# WIFIModule_M_V1_0.net
KiCad netlist of a schematic drawn in Altium Designer
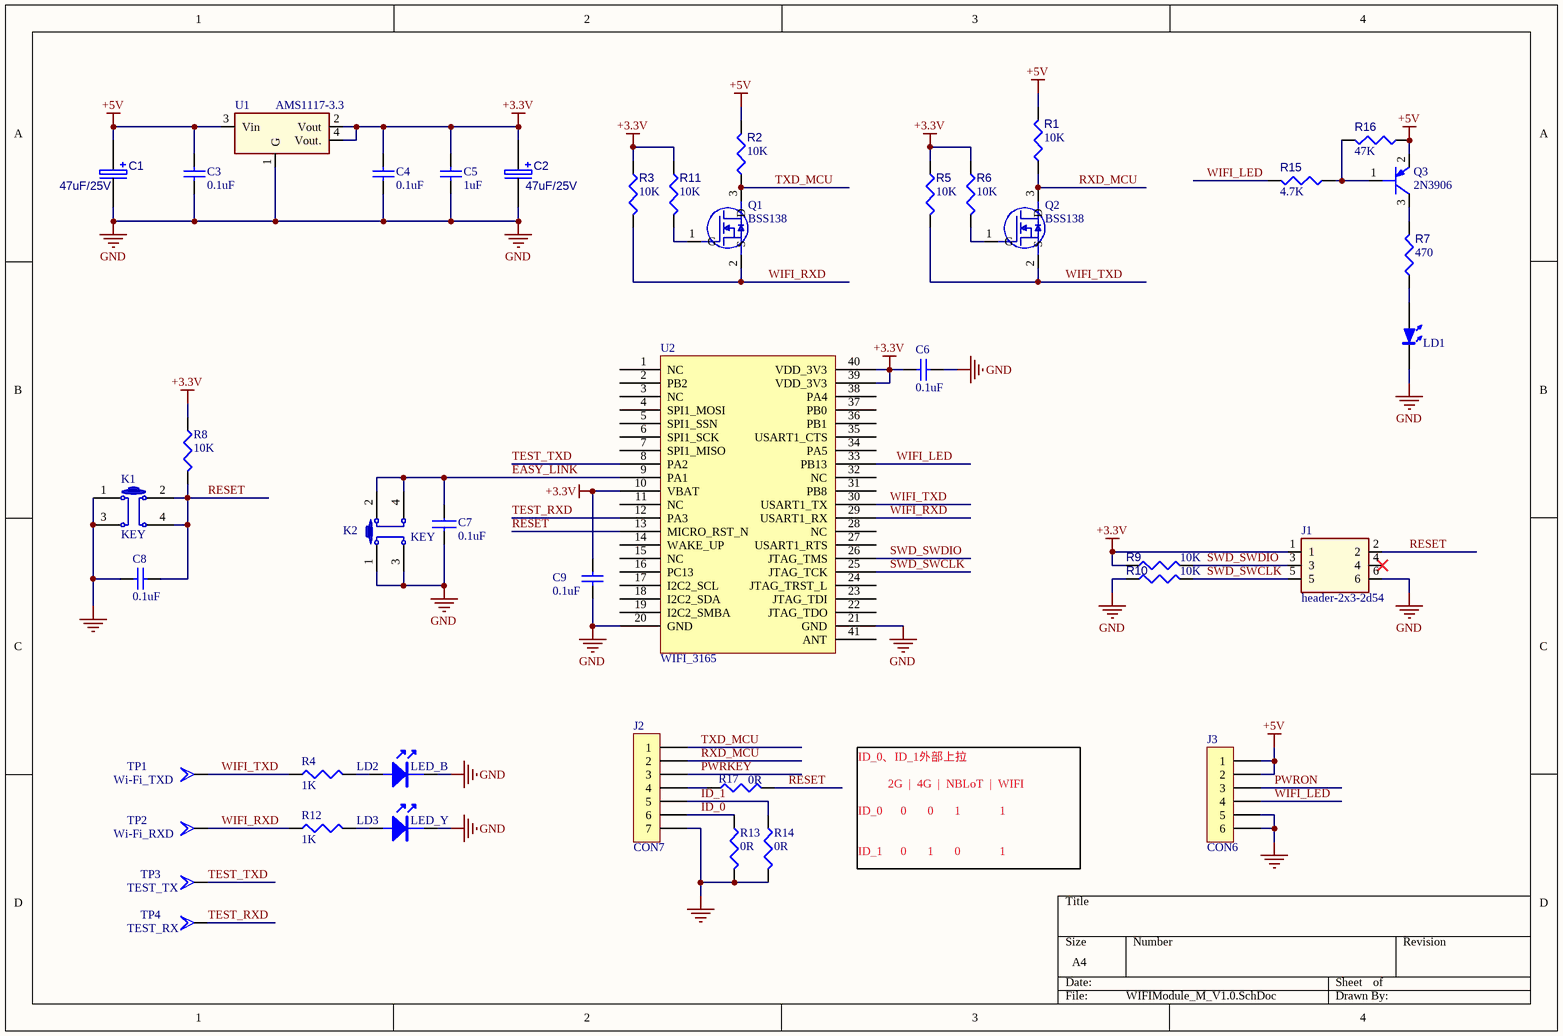
[diagram p0: WIFIModule_M_V1.0.SchDoc]

(export (version "E")
  (design (tool "Eeschema 10.0.6"))
  (components
    (comp (ref "C1")
      (value "47uF/25V")
      (footprint "C_TAN_B")
      (description "E-CAP")
      (libsource (lib "*") (part "ECAP"))
    )
    (comp (ref "C2")
      (value "47uF/25V")
      (footprint "C_TAN_B")
      (description "E-CAP")
      (libsource (lib "*") (part "ECAP"))
    )
    (comp (ref "C3")
      (value "0.1uF")
      (footprint "0603_C")
      (description "Capacitor")
      (fields (field (name "PUBLISHER") "Altium Limited"))
      (libsource (lib "EM_SENSOR_V3.01") (part "Cap Semi_1"))
    )
    (comp (ref "C4")
      (value "0.1uF")
      (footprint "0603_C")
      (description "Capacitor")
      (fields (field (name "PUBLISHER") "Altium Limited"))
      (libsource (lib "EM_SENSOR_V3.01") (part "Cap Semi_1"))
    )
    (comp (ref "C5")
      (value "1uF")
      (footprint "0603_C")
      (description "Capacitor")
      (fields (field (name "PUBLISHER") "Altium Limited"))
      (libsource (lib "EM_SENSOR_V3.01") (part "Cap Semi_1"))
    )
    (comp (ref "C6")
      (value "0.1uF")
      (footprint "0603_C")
      (description "Capacitor")
      (fields (field (name "PUBLISHER") "Altium Limited"))
      (libsource (lib "EM_SENSOR_V3.01") (part "Cap Semi_1"))
    )
    (comp (ref "C7") (value "0.1uF") (footprint "0603_C") (libsource (lib "EM_SENSOR_V4.1") (part "CAP NP")))
    (comp (ref "C8")
      (value "0.1uF")
      (footprint "0603_C")
      (description "Capacitor")
      (fields (field (name "PUBLISHER") "Altium Limited"))
      (libsource (lib "Miscellaneous Devices") (part "Cap"))
    )
    (comp (ref "C9")
      (value "0.1uF")
      (footprint "0603_C")
      (description "Capacitor")
      (fields (field (name "PUBLISHER") "Altium Limited"))
      (libsource (lib "EM_SENSOR_V2.03") (part "Cap Semi_1"))
    )
    (comp (ref "J1")
      (value "header-2x3-2d54")
      (footprint "HT8550_FLASH_LOADER")
      (libsource (lib "EM_SENSOR_V3.01") (part "header-2x3-2d54"))
    )
    (comp (ref "J2") (value "CON7") (footprint "SIP7") (libsource (lib "MySchlib") (part "CON7")))
    (comp (ref "J3") (value "CON6") (footprint "SIP6") (libsource (lib "MySchlib") (part "CON6")))
    (comp (ref "K1") (value "KEY") (footprint "KEY_SMD5465") (libsource (lib "") (part "KEY_1")))
    (comp (ref "K2") (value "KEY") (footprint "KEY_SMD5465") (libsource (lib "Schlib1") (part "KEY")))
    (comp (ref "LD1")
      (value "WHITE")
      (footprint "LED_0603")
      (description "LED")
      (libsource (lib "*") (part "LED"))
    )
    (comp (ref "LD2") (value "LED_B") (footprint "LED_0603") (libsource (lib "EM_SENSOR_V2.03") (part "LED")))
    (comp (ref "LD3") (value "LED_Y") (footprint "LED_0603") (libsource (lib "EM_SENSOR_V2.03") (part "LED")))
    (comp (ref "Q1")
      (value "BSS138")
      (footprint "SOT23")
      (description "N-Channel Enhancement MOSFET")
      (libsource (lib "EP_MCB_V6.0") (part "N-Channel Enhancement MOSFET"))
    )
    (comp (ref "Q2")
      (value "BSS138")
      (footprint "SOT23")
      (description "N-Channel Enhancement MOSFET")
      (libsource (lib "EP_MCB_V6.0") (part "N-Channel Enhancement MOSFET"))
    )
    (comp (ref "Q3") (value "2N3906") (footprint "SOT23") (libsource (lib "MySchlib") (part "PNP")))
    (comp (ref "R1")
      (value "10K")
      (footprint "0603_R")
      (description "Resistor")
      (fields (field (name "PUBLISHER") "Altium Limited"))
      (libsource (lib "EP_MCB_V6.0") (part "Res3_3"))
    )
    (comp (ref "R2")
      (value "10K")
      (footprint "0603_R")
      (description "Resistor")
      (fields (field (name "PUBLISHER") "Altium Limited"))
      (libsource (lib "EP_MCB_V6.0") (part "Res3_3"))
    )
    (comp (ref "R3")
      (value "10K")
      (footprint "0603_R")
      (description "Resistor")
      (fields (field (name "PUBLISHER") "Altium Limited"))
      (libsource (lib "EP_MCB_V6.0") (part "Res3_3"))
    )
    (comp (ref "R4") (value "1K") (footprint "0603_R") (libsource (lib "EM_SENSOR_V2.01") (part "R")))
    (comp (ref "R5")
      (value "10K")
      (footprint "0603_R")
      (description "Resistor")
      (fields (field (name "PUBLISHER") "Altium Limited"))
      (libsource (lib "EP_MCB_V6.0") (part "Res3_3"))
    )
    (comp (ref "R6")
      (value "10K")
      (footprint "0603_R")
      (description "Resistor")
      (fields (field (name "PUBLISHER") "Altium Limited"))
      (libsource (lib "EP_MCB_V6.0") (part "Res3_3"))
    )
    (comp (ref "R7")
      (value "470")
      (footprint "0603_R")
      (description "Resistor")
      (fields (field (name "PUBLISHER") "Altium Limited"))
      (libsource (lib "EM_SENSOR_V3.01") (part "Res3"))
    )
    (comp (ref "R8")
      (value "10K")
      (footprint "0603_R")
      (description "Resistor")
      (fields (field (name "PUBLISHER") "Altium Limited"))
      (libsource (lib "Miscellaneous Devices") (part "Res3"))
    )
    (comp (ref "R9")
      (value "10K")
      (footprint "0603_R")
      (description "Resistor")
      (fields (field (name "PUBLISHER") "Altium Limited"))
      (libsource (lib "EM_SENSOR_V3.01") (part "Res3"))
    )
    (comp (ref "R10")
      (value "10K")
      (footprint "0603_R")
      (description "Resistor")
      (fields (field (name "PUBLISHER") "Altium Limited"))
      (libsource (lib "EM_SENSOR_V3.01") (part "Res3"))
    )
    (comp (ref "R11")
      (value "10K")
      (footprint "0603_R")
      (description "Resistor")
      (fields (field (name "PUBLISHER") "Altium Limited"))
      (libsource (lib "EP_MCB_V6.0") (part "Res3_3"))
    )
    (comp (ref "R12") (value "1K") (footprint "0603_R") (libsource (lib "EM_SENSOR_V2.01") (part "R")))
    (comp (ref "R13") (value "0R") (footprint "0603_R") (libsource (lib "MySchlib") (part "RES1")))
    (comp (ref "R14") (value "0R") (footprint "0603_R") (libsource (lib "MySchlib") (part "RES1")))
    (comp (ref "R15")
      (value "4.7K")
      (footprint "0603_R")
      (description "Resistor")
      (fields (field (name "PUBLISHER") "Altium Limited"))
      (libsource (lib "EM_SENSOR_V3.01") (part "Res3"))
    )
    (comp (ref "R16")
      (value "47K")
      (footprint "0603_R")
      (description "Resistor")
      (fields (field (name "PUBLISHER") "Altium Limited"))
      (libsource (lib "EM_SENSOR_V3.01") (part "Res3"))
    )
    (comp (ref "R17") (value "0R") (footprint "0603_R") (libsource (lib "MySchlib") (part "RES1")))
    (comp (ref "TP1")
      (value "Wi-Fi_TXD")
      (footprint "TP_60_30")
      (libsource (lib "EM_SENSOR_V2.01") (part "T POINT A"))
    )
    (comp (ref "TP2")
      (value "Wi-Fi_RXD")
      (footprint "TP_60_30")
      (libsource (lib "EM_SENSOR_V2.01") (part "T POINT A"))
    )
    (comp (ref "TP3")
      (value "TEST_TX")
      (footprint "TP_60_30")
      (libsource (lib "EM_SENSOR_V2.03") (part "T POINT A"))
    )
    (comp (ref "TP4")
      (value "TEST_RX")
      (footprint "TP_60_30")
      (libsource (lib "EM_SENSOR_V2.03") (part "T POINT A"))
    )
    (comp (ref "U1")
      (value "AMS1117-3.3")
      (footprint "SOT223")
      (libsource (lib "EM_SENSOR_V2.01") (part "AMS1117-3.3"))
    )
    (comp (ref "U2") (value "WIFI_3165") (footprint "EMW3165-P") (libsource (lib "*") (part "WIFI_3165")))
  )
  (nets
    (net (code "1") (name "+3.3V") (class "Default")
      (node (ref "C2") (pin "1") (pinfunction "+_1") (pintype "passive"))
      (node (ref "C4") (pin "1") (pinfunction "1_1") (pintype "passive"))
      (node (ref "C5") (pin "1") (pinfunction "1_1") (pintype "passive"))
      (node (ref "C6") (pin "2") (pinfunction "2_2") (pintype "passive"))
      (node (ref "C9") (pin "2") (pinfunction "2_2") (pintype "passive"))
      (node (ref "J1") (pin "1") (pinfunction "1_1") (pintype "passive"))
      (node (ref "R11") (pin "1") (pinfunction "1_1") (pintype "passive"))
      (node (ref "R3") (pin "1") (pinfunction "1_1") (pintype "passive"))
      (node (ref "R5") (pin "1") (pinfunction "1_1") (pintype "passive"))
      (node (ref "R6") (pin "1") (pinfunction "1_1") (pintype "passive"))
      (node (ref "R8") (pin "2") (pinfunction "2_2") (pintype "passive"))
      (node (ref "R9") (pin "1") (pinfunction "1_1") (pintype "passive"))
      (node (ref "U1") (pin "2") (pinfunction "Vout_2") (pintype "passive"))
      (node (ref "U1") (pin "4") (pinfunction "Vout._4") (pintype "passive"))
      (node (ref "U2") (pin "10") (pinfunction "VBAT_10") (pintype "passive"))
      (node (ref "U2") (pin "39") (pinfunction "VDD_3V3_39") (pintype "passive"))
      (node (ref "U2") (pin "40") (pinfunction "VDD_3V3_40") (pintype "passive"))
    )
    (net (code "2") (name "+5V") (class "Default")
      (node (ref "C1") (pin "1") (pinfunction "+_1") (pintype "passive"))
      (node (ref "C3") (pin "1") (pinfunction "1_1") (pintype "passive"))
      (node (ref "J3") (pin "1") (pinfunction "1_1") (pintype "passive"))
      (node (ref "J3") (pin "2") (pinfunction "2_2") (pintype "passive"))
      (node (ref "Q3") (pin "2") (pinfunction "EMITTER_2") (pintype "passive"))
      (node (ref "R1") (pin "2") (pinfunction "2_2") (pintype "passive"))
      (node (ref "R16") (pin "1") (pinfunction "1_1") (pintype "passive"))
      (node (ref "R2") (pin "2") (pinfunction "2_2") (pintype "passive"))
      (node (ref "U1") (pin "3") (pinfunction "Vin_3") (pintype "passive"))
    )
    (net (code "3") (name "/EASY_LINK") (class "Default")
      (node (ref "C7") (pin "1") (pinfunction "1_1") (pintype "passive"))
      (node (ref "K2") (pin "2") (pinfunction "2_2") (pintype "passive"))
      (node (ref "K2") (pin "4") (pinfunction "4_4") (pintype "passive"))
      (node (ref "U2") (pin "9") (pinfunction "PA1_9") (pintype "passive"))
    )
    (net (code "4") (name "/ID_0") (class "Default")
      (node (ref "J2") (pin "6") (pinfunction "6_6") (pintype "passive"))
      (node (ref "R13") (pin "1") (pinfunction "1_1") (pintype "passive"))
    )
    (net (code "5") (name "/ID_1") (class "Default")
      (node (ref "J2") (pin "5") (pinfunction "5_5") (pintype "passive"))
      (node (ref "R14") (pin "1") (pinfunction "1_1") (pintype "passive"))
    )
    (net (code "6") (name "/PWRKEY") (class "Default")
      (node (ref "J2") (pin "3") (pinfunction "3_3") (pintype "passive"))
    )
    (net (code "7") (name "/PWRON") (class "Default")
      (node (ref "J3") (pin "3") (pinfunction "3_3") (pintype "passive"))
    )
    (net (code "8") (name "/RESET") (class "Default")
      (node (ref "C8") (pin "2") (pinfunction "2_2") (pintype "passive"))
      (node (ref "J1") (pin "2") (pinfunction "2_2") (pintype "passive"))
      (node (ref "K1") (pin "2") (pinfunction "2_2") (pintype "passive"))
      (node (ref "K1") (pin "4") (pinfunction "4_4") (pintype "passive"))
      (node (ref "R17") (pin "2") (pinfunction "2_2") (pintype "passive"))
      (node (ref "R8") (pin "1") (pinfunction "1_1") (pintype "passive"))
      (node (ref "U2") (pin "13") (pinfunction "MICRO_RST_N_13") (pintype "passive"))
    )
    (net (code "9") (name "/RXD_MCU") (class "Default")
      (node (ref "J2") (pin "2") (pinfunction "2_2") (pintype "passive"))
      (node (ref "Q2") (pin "3") (pinfunction "D_3") (pintype "passive"))
      (node (ref "R1") (pin "1") (pinfunction "1_1") (pintype "passive"))
    )
    (net (code "10") (name "/SWD_SWCLK") (class "Default")
      (node (ref "J1") (pin "5") (pinfunction "5_5") (pintype "passive"))
      (node (ref "R10") (pin "2") (pinfunction "2_2") (pintype "passive"))
      (node (ref "U2") (pin "25") (pinfunction "JTAG_TCK_25") (pintype "passive"))
    )
    (net (code "11") (name "/SWD_SWDIO") (class "Default")
      (node (ref "J1") (pin "3") (pinfunction "3_3") (pintype "passive"))
      (node (ref "R9") (pin "2") (pinfunction "2_2") (pintype "passive"))
      (node (ref "U2") (pin "26") (pinfunction "JTAG_TMS_26") (pintype "passive"))
    )
    (net (code "12") (name "/TEST_RXD") (class "Default")
      (node (ref "TP4") (pin "1") (pinfunction "TP_1") (pintype "passive"))
      (node (ref "U2") (pin "12") (pinfunction "PA3_12") (pintype "passive"))
    )
    (net (code "13") (name "/TEST_TXD") (class "Default")
      (node (ref "TP3") (pin "1") (pinfunction "TP_1") (pintype "passive"))
      (node (ref "U2") (pin "8") (pinfunction "PA2_8") (pintype "passive"))
    )
    (net (code "14") (name "/TXD_MCU") (class "Default")
      (node (ref "J2") (pin "1") (pinfunction "1_1") (pintype "passive"))
      (node (ref "Q1") (pin "3") (pinfunction "D_3") (pintype "passive"))
      (node (ref "R2") (pin "1") (pinfunction "1_1") (pintype "passive"))
    )
    (net (code "15") (name "/WIFI_LED") (class "Default")
      (node (ref "J3") (pin "4") (pinfunction "4_4") (pintype "passive"))
      (node (ref "R15") (pin "2") (pinfunction "2_2") (pintype "passive"))
      (node (ref "U2") (pin "33") (pinfunction "PB13_33") (pintype "passive"))
    )
    (net (code "16") (name "/WIFI_RXD") (class "Default")
      (node (ref "Q1") (pin "2") (pinfunction "S_2") (pintype "passive"))
      (node (ref "R12") (pin "1") (pinfunction "1_1") (pintype "passive"))
      (node (ref "R3") (pin "2") (pinfunction "2_2") (pintype "passive"))
      (node (ref "TP2") (pin "1") (pinfunction "TP_1") (pintype "passive"))
      (node (ref "U2") (pin "29") (pinfunction "USART1_RX_29") (pintype "passive"))
    )
    (net (code "17") (name "/WIFI_TXD") (class "Default")
      (node (ref "Q2") (pin "2") (pinfunction "S_2") (pintype "passive"))
      (node (ref "R4") (pin "1") (pinfunction "1_1") (pintype "passive"))
      (node (ref "R5") (pin "2") (pinfunction "2_2") (pintype "passive"))
      (node (ref "TP1") (pin "1") (pinfunction "TP_1") (pintype "passive"))
      (node (ref "U2") (pin "30") (pinfunction "USART1_TX_30") (pintype "passive"))
    )
    (net (code "18") (name "GND") (class "Default")
      (node (ref "C1") (pin "2") (pinfunction "-_2") (pintype "passive"))
      (node (ref "C2") (pin "2") (pinfunction "-_2") (pintype "passive"))
      (node (ref "C3") (pin "2") (pinfunction "2_2") (pintype "passive"))
      (node (ref "C4") (pin "2") (pinfunction "2_2") (pintype "passive"))
      (node (ref "C5") (pin "2") (pinfunction "2_2") (pintype "passive"))
      (node (ref "C6") (pin "1") (pinfunction "1_1") (pintype "passive"))
      (node (ref "C7") (pin "2") (pinfunction "2_2") (pintype "passive"))
      (node (ref "C8") (pin "1") (pinfunction "1_1") (pintype "passive"))
      (node (ref "C9") (pin "1") (pinfunction "1_1") (pintype "passive"))
      (node (ref "J1") (pin "6") (pinfunction "6_6") (pintype "passive"))
      (node (ref "J2") (pin "7") (pinfunction "7_7") (pintype "passive"))
      (node (ref "J3") (pin "5") (pinfunction "5_5") (pintype "passive"))
      (node (ref "J3") (pin "6") (pinfunction "6_6") (pintype "passive"))
      (node (ref "K1") (pin "1") (pinfunction "1_1") (pintype "passive"))
      (node (ref "K1") (pin "3") (pinfunction "3_3") (pintype "passive"))
      (node (ref "K2") (pin "1") (pinfunction "1_1") (pintype "passive"))
      (node (ref "K2") (pin "3") (pinfunction "3_3") (pintype "passive"))
      (node (ref "LD1") (pin "K") (pinfunction "K_K") (pintype "passive"))
      (node (ref "LD2") (pin "K") (pinfunction "2_K") (pintype "passive"))
      (node (ref "LD3") (pin "K") (pinfunction "2_K") (pintype "passive"))
      (node (ref "R10") (pin "1") (pinfunction "1_1") (pintype "passive"))
      (node (ref "R13") (pin "2") (pinfunction "2_2") (pintype "passive"))
      (node (ref "R14") (pin "2") (pinfunction "2_2") (pintype "passive"))
      (node (ref "U1") (pin "1") (pinfunction "G_1") (pintype "passive"))
      (node (ref "U2") (pin "20") (pinfunction "GND_20") (pintype "passive"))
      (node (ref "U2") (pin "21") (pinfunction "GND_21") (pintype "passive"))
    )
    (net (code "19") (name "Net-(J2-Pad4)") (class "Default")
      (node (ref "J2") (pin "4") (pinfunction "4_4") (pintype "passive"))
      (node (ref "R17") (pin "1") (pinfunction "1_1") (pintype "passive"))
    )
    (net (code "20") (name "Net-(LD1-PadA)") (class "Default")
      (node (ref "LD1") (pin "A") (pinfunction "A_A") (pintype "passive"))
      (node (ref "R7") (pin "1") (pinfunction "1_1") (pintype "passive"))
    )
    (net (code "21") (name "Net-(LD2-1)") (class "Default")
      (node (ref "LD2") (pin "A") (pinfunction "1_A") (pintype "passive"))
      (node (ref "R4") (pin "2") (pinfunction "2_2") (pintype "passive"))
    )
    (net (code "22") (name "Net-(LD3-1)") (class "Default")
      (node (ref "LD3") (pin "A") (pinfunction "1_A") (pintype "passive"))
      (node (ref "R12") (pin "2") (pinfunction "2_2") (pintype "passive"))
    )
    (net (code "23") (name "Net-(Q1-G)") (class "Default")
      (node (ref "Q1") (pin "1") (pinfunction "G_1") (pintype "passive"))
      (node (ref "R11") (pin "2") (pinfunction "2_2") (pintype "passive"))
    )
    (net (code "24") (name "Net-(Q2-G)") (class "Default")
      (node (ref "Q2") (pin "1") (pinfunction "G_1") (pintype "passive"))
      (node (ref "R6") (pin "2") (pinfunction "2_2") (pintype "passive"))
    )
    (net (code "25") (name "Net-(Q3-BASE)") (class "Default")
      (node (ref "Q3") (pin "1") (pinfunction "BASE_1") (pintype "passive"))
      (node (ref "R15") (pin "1") (pinfunction "1_1") (pintype "passive"))
      (node (ref "R16") (pin "2") (pinfunction "2_2") (pintype "passive"))
    )
    (net (code "26") (name "Net-(Q3-COLLECTOR)") (class "Default")
      (node (ref "Q3") (pin "3") (pinfunction "COLLECTOR_3") (pintype "passive"))
      (node (ref "R7") (pin "2") (pinfunction "2_2") (pintype "passive"))
    )
    (net (code "27") (name "unconnected-(J1-Pad4)") (class "Default")
      (node (ref "J1") (pin "4") (pinfunction "4_4") (pintype "passive+no_connect"))
    )
    (net (code "28") (name "unconnected-(U2-ANT-Pad41)") (class "Default")
      (node (ref "U2") (pin "41") (pinfunction "ANT_41") (pintype "passive"))
    )
    (net (code "29") (name "unconnected-(U2-I2C2_SCL-Pad17)") (class "Default")
      (node (ref "U2") (pin "17") (pinfunction "I2C2_SCL_17") (pintype "passive"))
    )
    (net (code "30") (name "unconnected-(U2-I2C2_SDA-Pad18)") (class "Default")
      (node (ref "U2") (pin "18") (pinfunction "I2C2_SDA_18") (pintype "passive"))
    )
    (net (code "31") (name "unconnected-(U2-I2C2_SMBA-Pad19)") (class "Default")
      (node (ref "U2") (pin "19") (pinfunction "I2C2_SMBA_19") (pintype "passive"))
    )
    (net (code "32") (name "unconnected-(U2-JTAG_TDI-Pad23)") (class "Default")
      (node (ref "U2") (pin "23") (pinfunction "JTAG_TDI_23") (pintype "passive"))
    )
    (net (code "33") (name "unconnected-(U2-JTAG_TDO-Pad22)") (class "Default")
      (node (ref "U2") (pin "22") (pinfunction "JTAG_TDO_22") (pintype "passive"))
    )
    (net (code "34") (name "unconnected-(U2-JTAG_TRST_L-Pad24)") (class "Default")
      (node (ref "U2") (pin "24") (pinfunction "JTAG_TRST_L_24") (pintype "passive"))
    )
    (net (code "35") (name "unconnected-(U2-NC-Pad1)") (class "Default")
      (node (ref "U2") (pin "1") (pinfunction "NC_1") (pintype "passive"))
    )
    (net (code "36") (name "unconnected-(U2-NC-Pad3)") (class "Default")
      (node (ref "U2") (pin "3") (pinfunction "NC_3") (pintype "passive"))
    )
    (net (code "37") (name "unconnected-(U2-NC-Pad11)") (class "Default")
      (node (ref "U2") (pin "11") (pinfunction "NC_11") (pintype "passive"))
    )
    (net (code "38") (name "unconnected-(U2-NC-Pad15)") (class "Default")
      (node (ref "U2") (pin "15") (pinfunction "NC_15") (pintype "passive"))
    )
    (net (code "39") (name "unconnected-(U2-NC-Pad28)") (class "Default")
      (node (ref "U2") (pin "28") (pinfunction "NC_28") (pintype "passive"))
    )
    (net (code "40") (name "unconnected-(U2-NC-Pad32)") (class "Default")
      (node (ref "U2") (pin "32") (pinfunction "NC_32") (pintype "passive"))
    )
    (net (code "41") (name "unconnected-(U2-PA4-Pad38)") (class "Default")
      (node (ref "U2") (pin "38") (pinfunction "PA4_38") (pintype "passive"))
    )
    (net (code "42") (name "unconnected-(U2-PA5-Pad34)") (class "Default")
      (node (ref "U2") (pin "34") (pinfunction "PA5_34") (pintype "passive"))
    )
    (net (code "43") (name "unconnected-(U2-PB0-Pad37)") (class "Default")
      (node (ref "U2") (pin "37") (pinfunction "PB0_37") (pintype "passive"))
    )
    (net (code "44") (name "unconnected-(U2-PB1-Pad36)") (class "Default")
      (node (ref "U2") (pin "36") (pinfunction "PB1_36") (pintype "passive"))
    )
    (net (code "45") (name "unconnected-(U2-PB2-Pad2)") (class "Default")
      (node (ref "U2") (pin "2") (pinfunction "PB2_2") (pintype "passive"))
    )
    (net (code "46") (name "unconnected-(U2-PB8-Pad31)") (class "Default")
      (node (ref "U2") (pin "31") (pinfunction "PB8_31") (pintype "passive"))
    )
    (net (code "47") (name "unconnected-(U2-PC13-Pad16)") (class "Default")
      (node (ref "U2") (pin "16") (pinfunction "PC13_16") (pintype "passive"))
    )
    (net (code "48") (name "unconnected-(U2-SPI1_MISO-Pad7)") (class "Default")
      (node (ref "U2") (pin "7") (pinfunction "SPI1_MISO_7") (pintype "passive"))
    )
    (net (code "49") (name "unconnected-(U2-SPI1_MOSI-Pad4)") (class "Default")
      (node (ref "U2") (pin "4") (pinfunction "SPI1_MOSI_4") (pintype "passive"))
    )
    (net (code "50") (name "unconnected-(U2-SPI1_SCK-Pad6)") (class "Default")
      (node (ref "U2") (pin "6") (pinfunction "SPI1_SCK_6") (pintype "passive"))
    )
    (net (code "51") (name "unconnected-(U2-SPI1_SSN-Pad5)") (class "Default")
      (node (ref "U2") (pin "5") (pinfunction "SPI1_SSN_5") (pintype "passive"))
    )
    (net (code "52") (name "unconnected-(U2-USART1_CTS-Pad35)") (class "Default")
      (node (ref "U2") (pin "35") (pinfunction "USART1_CTS_35") (pintype "passive"))
    )
    (net (code "53") (name "unconnected-(U2-USART1_RTS-Pad27)") (class "Default")
      (node (ref "U2") (pin "27") (pinfunction "USART1_RTS_27") (pintype "passive"))
    )
    (net (code "54") (name "unconnected-(U2-WAKE_UP-Pad14)") (class "Default")
      (node (ref "U2") (pin "14") (pinfunction "WAKE_UP_14") (pintype "passive"))
    )
  )
)
